# LPTSV2_usingATmega328PV6.net
KiCad netlist of a schematic drawn in EAGLE
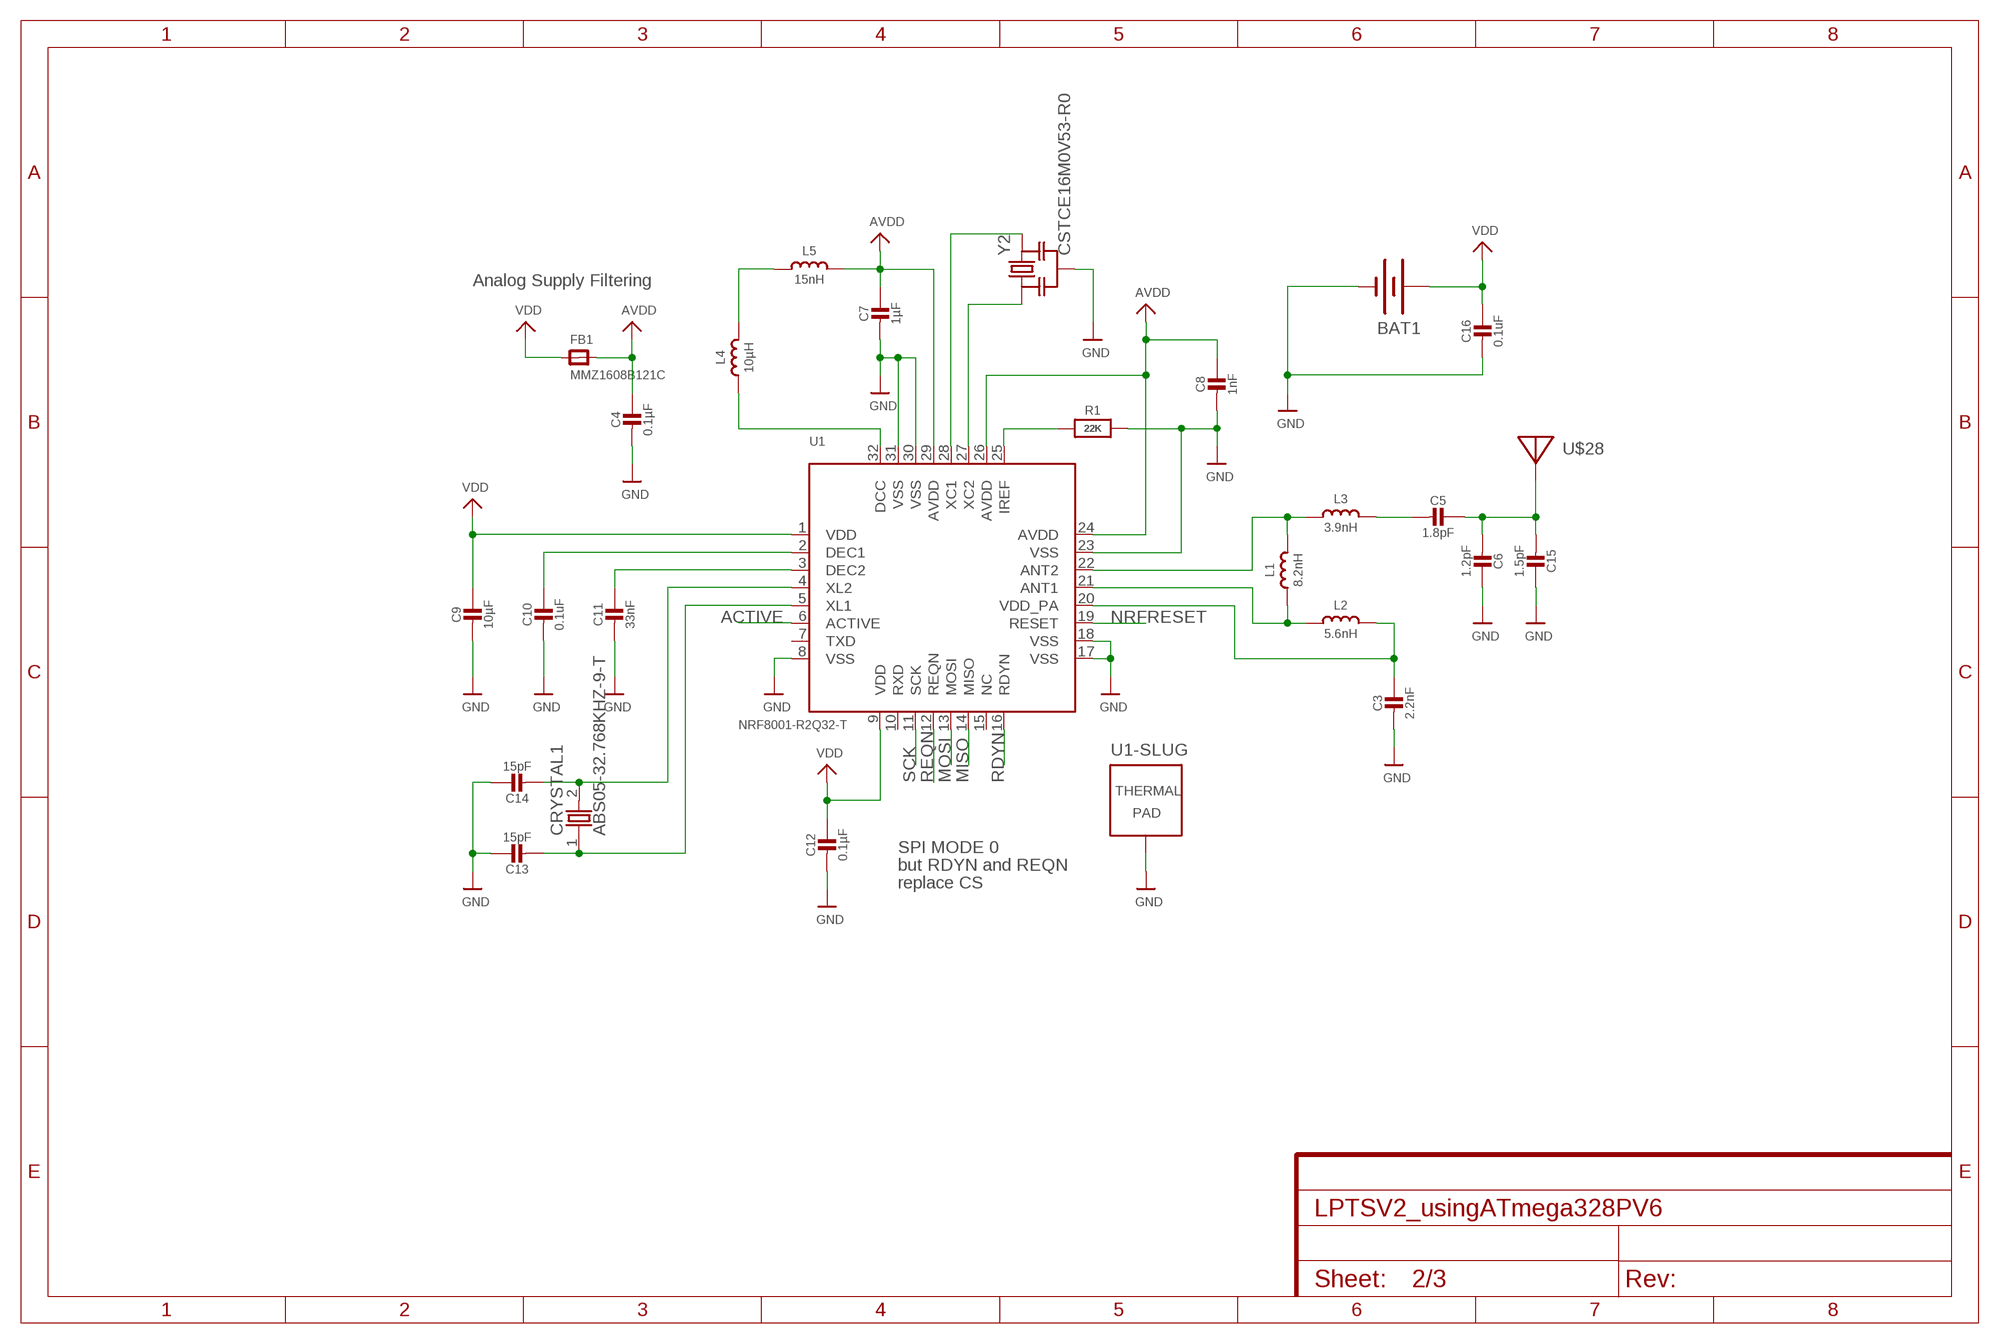
[diagram p0: schematic, sheet 2]
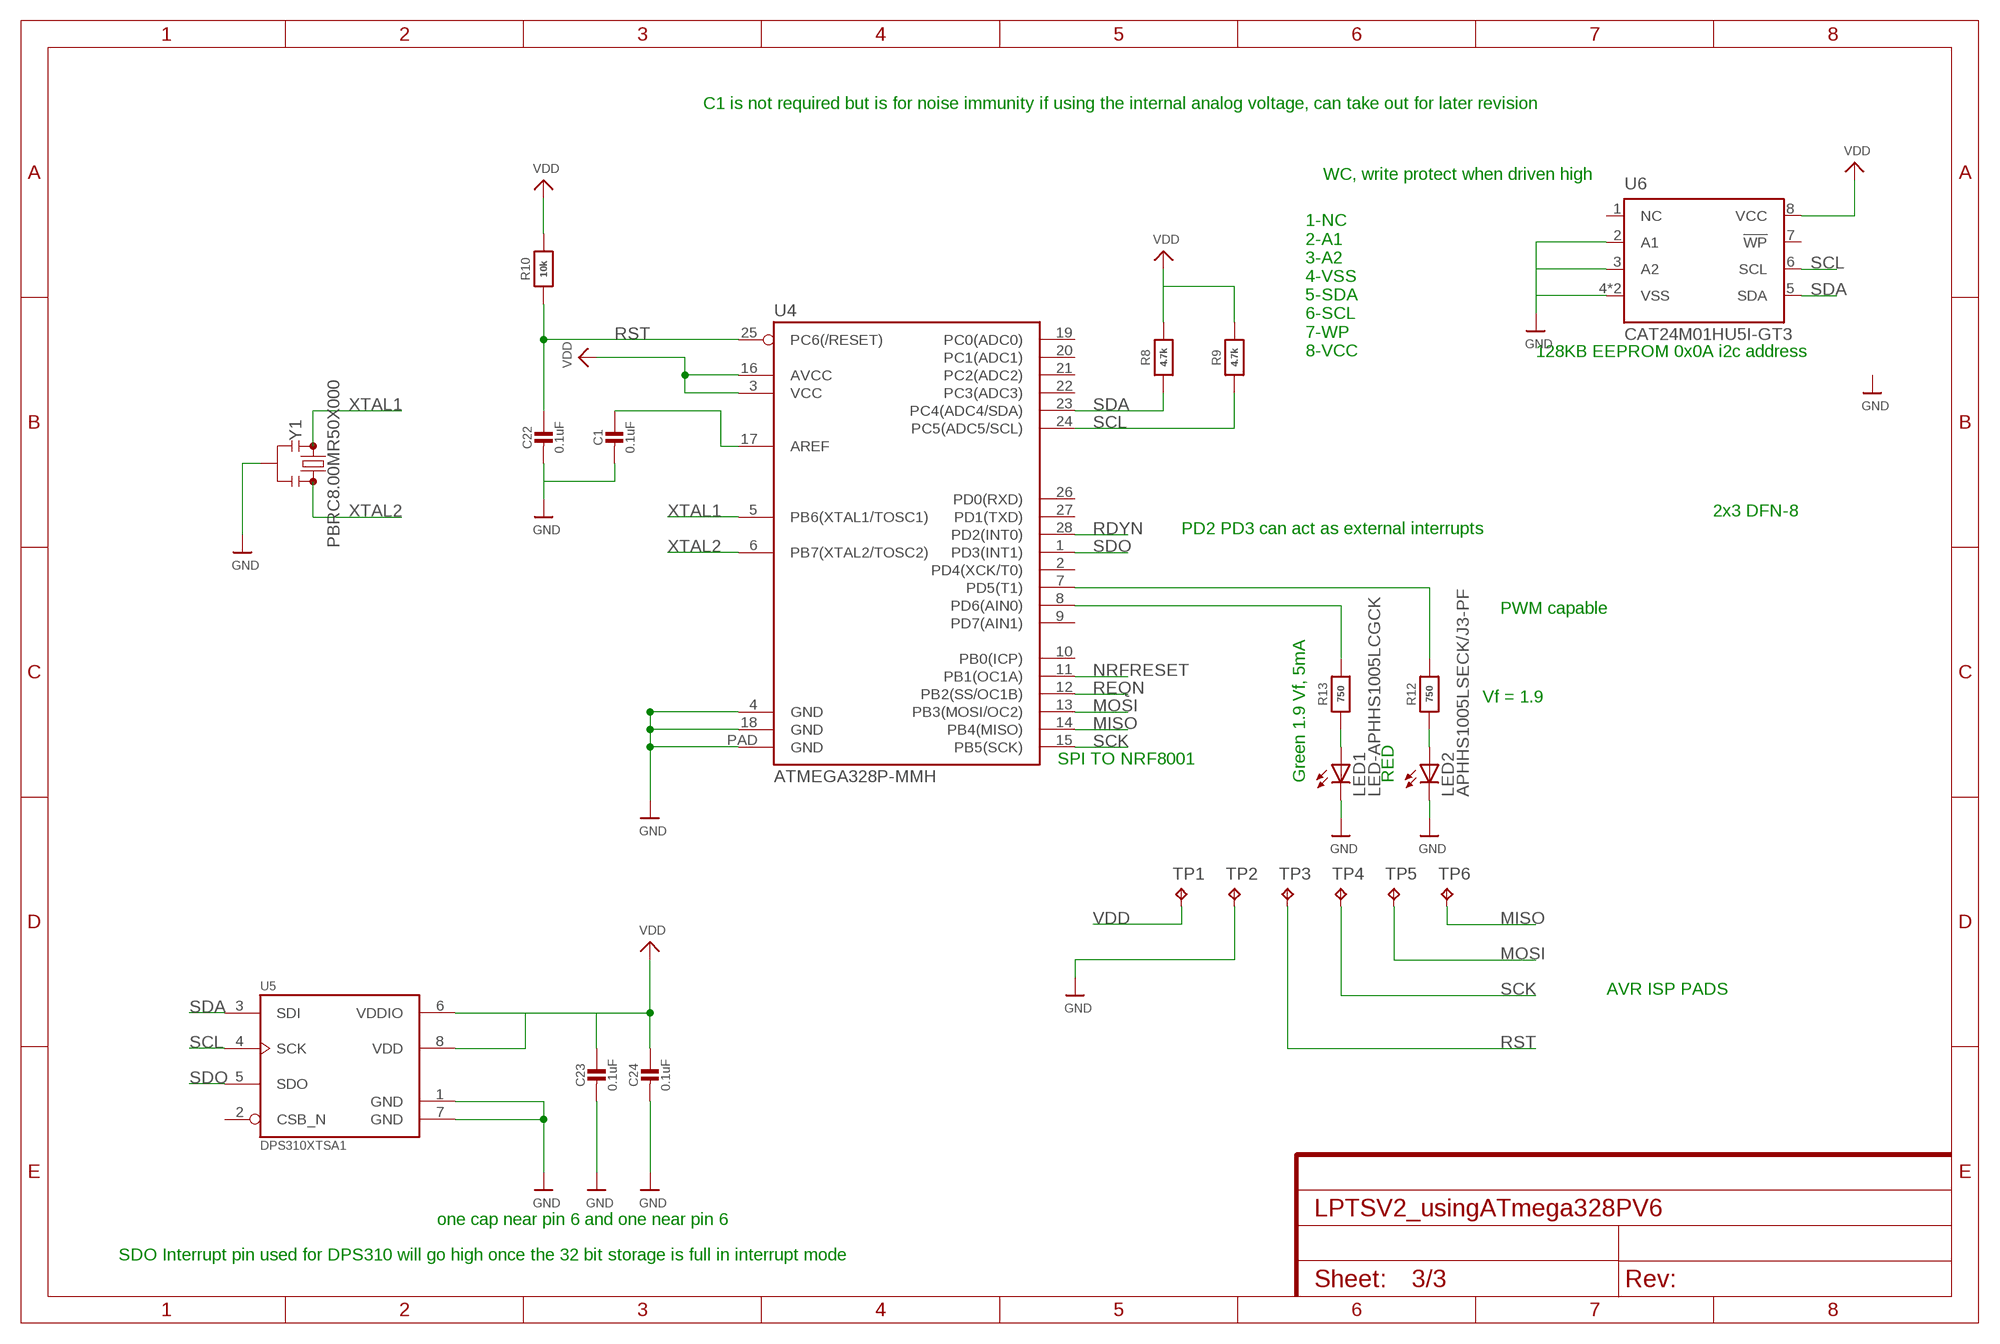
[diagram p1: schematic, sheet 3]

(export (version "E")
  (design (tool "Eeschema 10.0.6"))
  (components
    (comp (ref "C1")
      (value "0.1uF")
      (footprint "eagle-import:_0402")
      (fields (field (name "PARTNUMBER") "GRM155R71C104KA88J"))
      (libsource (lib "eagle-import") (part "CAP_CERAMIC_0402"))
    )
    (comp (ref "C22")
      (value "0.1uF")
      (footprint "eagle-import:_0402")
      (fields (field (name "PARTNUMBER") "GRM155R71C104KA88J"))
      (libsource (lib "eagle-import") (part "CAP_CERAMIC_0402"))
    )
    (comp (ref "C23")
      (value "0.1uF")
      (footprint "eagle-import:_0402")
      (fields (field (name "PARTNUMBER") "GRM155R71C104KA88J"))
      (libsource (lib "eagle-import") (part "CAP_CERAMIC_0402"))
    )
    (comp (ref "C24")
      (value "0.1uF")
      (footprint "eagle-import:_0402")
      (fields (field (name "PARTNUMBER") "GRM155R71C104KA88J"))
      (libsource (lib "eagle-import") (part "CAP_CERAMIC_0402"))
    )
    (comp (ref "LED1")
      (value "LED-APHHS1005LCGCK")
      (footprint "eagle-import:0402-LED")
      (libsource (lib "eagle-import") (part "LED-0402"))
    )
    (comp (ref "LED2")
      (value "APHHS1005LSECK/J3-PF")
      (footprint "eagle-import:0402-LED")
      (libsource (lib "eagle-import") (part "LED-0402"))
    )
    (comp (ref "R8")
      (value "4.7k")
      (footprint "eagle-import:_0402")
      (fields (field (name "PARTNUMBER") "RC0402JR-074K7L"))
      (libsource (lib "eagle-import") (part "RESISTOR_0402"))
    )
    (comp (ref "R9")
      (value "4.7k")
      (footprint "eagle-import:_0402")
      (fields (field (name "PARTNUMBER") "RC0402JR-074K7L"))
      (libsource (lib "eagle-import") (part "RESISTOR_0402"))
    )
    (comp (ref "R10")
      (value "10k")
      (footprint "eagle-import:_0402")
      (fields (field (name "PARTNUMBER") "RC0402JR-0710KL"))
      (libsource (lib "eagle-import") (part "RESISTOR_0402"))
    )
    (comp (ref "R12")
      (value "750")
      (footprint "eagle-import:_0402")
      (fields (field (name "PARTNUMBER") "RC0402JR-07750RL"))
      (libsource (lib "eagle-import") (part "RESISTOR_0402"))
    )
    (comp (ref "R13")
      (value "750")
      (footprint "eagle-import:_0402")
      (fields (field (name "PARTNUMBER") "RC0402JR-07750RL"))
      (libsource (lib "eagle-import") (part "RESISTOR_0402"))
    )
    (comp (ref "TP1")
      (value "TPTP10SQ")
      (footprint "eagle-import:TP10SQ")
      (libsource (lib "eagle-import") (part "TPTP10SQ"))
    )
    (comp (ref "TP2")
      (value "TPTP10SQ")
      (footprint "eagle-import:TP10SQ")
      (libsource (lib "eagle-import") (part "TPTP10SQ"))
    )
    (comp (ref "TP3")
      (value "TPTP10SQ")
      (footprint "eagle-import:TP10SQ")
      (libsource (lib "eagle-import") (part "TPTP10SQ"))
    )
    (comp (ref "TP4")
      (value "TPTP10SQ")
      (footprint "eagle-import:TP10SQ")
      (libsource (lib "eagle-import") (part "TPTP10SQ"))
    )
    (comp (ref "TP5")
      (value "TPTP10SQ")
      (footprint "eagle-import:TP10SQ")
      (libsource (lib "eagle-import") (part "TPTP10SQ"))
    )
    (comp (ref "TP6")
      (value "TPTP10SQ")
      (footprint "eagle-import:TP10SQ")
      (libsource (lib "eagle-import") (part "TPTP10SQ"))
    )
    (comp (ref "U4")
      (value "ATMEGA328P-MMH")
      (footprint "eagle-import:SPARKFUN-IC-MICROCONTROLLER_VQFN-28")
      (libsource (lib "eagle-import") (part "SPARKFUN-IC-MICROCONTROLLER_ATMEGA328P_VQFNVQFN"))
    )
    (comp (ref "U5")
      (value "DPS310XTSA1")
      (footprint "eagle-import:LGA8S145X65P2X4_200X250X100")
      (libsource (lib "eagle-import") (part "DPS310"))
    )
    (comp (ref "U6")
      (value "CAT24M01HU5I-GT3")
      (footprint "eagle-import:DFN-2X3")
      (libsource (lib "eagle-import") (part "CAT24M01HU5I-GT3"))
    )
    (comp (ref "Y1")
      (value "PBRC8.00MR50X000")
      (footprint "eagle-import:RESONATOR-SMD-4.5X2.0")
      (libsource (lib "eagle-import") (part "RESONATOR-4MHZSMD-4.5X2"))
    )
    (comp (ref "BAT1")
      (value "LINX-BAT-HLD-00120SMD")
      (footprint "eagle-import:BATTCON_20MM")
      (fields (field (name "PARTNUMBER") "BAT-HLD-001-TRCT-ND"))
      (libsource (lib "eagle-import") (part "LINX-BAT-HLD-00120SMD"))
    )
    (comp (ref "C3")
      (value "2.2nF")
      (footprint "eagle-import:_0402")
      (fields (field (name "PARTNUMBER") "C0402C222J8JAC7867"))
      (libsource (lib "eagle-import") (part "CAP_CERAMIC_0402"))
    )
    (comp (ref "C4")
      (value "0.1µF")
      (footprint "eagle-import:_0402")
      (fields (field (name "PARTNUMBER") "GRM155R71C104KA88J"))
      (libsource (lib "eagle-import") (part "CAP_CERAMIC_0402"))
    )
    (comp (ref "C5")
      (value "1.8pF")
      (footprint "eagle-import:_0402MP")
      (fields (field (name "PARTNUMBER") "GRM1555C1E1R8BA01D"))
      (libsource (lib "eagle-import") (part "CAP_CERAMIC_0402MP"))
    )
    (comp (ref "C6")
      (value "1.2pF")
      (footprint "eagle-import:_0402MP")
      (fields (field (name "PARTNUMBER") "GRM1555C1E1R2BA01D"))
      (libsource (lib "eagle-import") (part "CAP_CERAMIC_0402MP"))
    )
    (comp (ref "C7")
      (value "1µF")
      (footprint "eagle-import:_0402")
      (fields (field (name "PARTNUMBER") "0402ZD105KAT2A"))
      (libsource (lib "eagle-import") (part "CAP_CERAMIC_0402"))
    )
    (comp (ref "C8")
      (value "1nF")
      (footprint "eagle-import:_0402")
      (fields (field (name "PARTNUMBER") "GRM155R71H102KA01D"))
      (libsource (lib "eagle-import") (part "CAP_CERAMIC_0402"))
    )
    (comp (ref "C9")
      (value "10µF")
      (footprint "eagle-import:_0402")
      (fields (field (name "PARTNUMBER") "GRM155R60J106ME15D"))
      (libsource (lib "eagle-import") (part "CAP_CERAMIC_0402"))
    )
    (comp (ref "C10")
      (value "0.1uF")
      (footprint "eagle-import:_0402")
      (fields (field (name "PARTNUMBER") "GRM155R71C104KA88J"))
      (libsource (lib "eagle-import") (part "CAP_CERAMIC_0402"))
    )
    (comp (ref "C11")
      (value "33nF")
      (footprint "eagle-import:_0402")
      (fields (field (name "PARTNUMBER") "C0402C333K8RACTU"))
      (libsource (lib "eagle-import") (part "CAP_CERAMIC_0402"))
    )
    (comp (ref "C12")
      (value "0.1µF")
      (footprint "eagle-import:_0402")
      (fields (field (name "PARTNUMBER") "GRM155R71C104KA88J"))
      (libsource (lib "eagle-import") (part "CAP_CERAMIC_0402"))
    )
    (comp (ref "C13")
      (value "15pF")
      (footprint "eagle-import:_0402")
      (fields (field (name "PARTNUMBER") "GRM1555C1H150JA01D"))
      (libsource (lib "eagle-import") (part "CAP_CERAMIC_0402"))
    )
    (comp (ref "C14")
      (value "15pF")
      (footprint "eagle-import:_0402")
      (fields (field (name "PARTNUMBER") "GRM1555C1H150JA01D"))
      (libsource (lib "eagle-import") (part "CAP_CERAMIC_0402"))
    )
    (comp (ref "C15")
      (value "1.5pF")
      (footprint "eagle-import:_0402MP")
      (fields (field (name "PARTNUMBER") "GRM1555C1H1R5BA01D"))
      (libsource (lib "eagle-import") (part "CAP_CERAMIC_0402MP"))
    )
    (comp (ref "C16")
      (value "0.1uF")
      (footprint "eagle-import:_0402")
      (fields (field (name "PARTNUMBER") "GRM155R71C104KA88J"))
      (libsource (lib "eagle-import") (part "CAP_CERAMIC_0402"))
    )
    (comp (ref "CRYSTAL1")
      (value "ABS05-32.768KHZ-9-T")
      (footprint "eagle-import:CRYSTAL-2PIN")
      (libsource (lib "eagle-import") (part "CRYSTAL2PIN"))
    )
    (comp (ref "FB1")
      (value "MMZ1608B121C")
      (footprint "eagle-import:0805")
      (fields (field (name "PARTNUMBER") "MMZ1608B121CTDH5"))
      (libsource (lib "eagle-import") (part "FERRITE0805"))
    )
    (comp (ref "L1")
      (value "8.2nH")
      (footprint "eagle-import:_0402")
      (fields (field (name "PARTNUMBER") "LQP15MN8N2B02D"))
      (libsource (lib "eagle-import") (part "INDUCTOR_0402"))
    )
    (comp (ref "L2")
      (value "5.6nH")
      (footprint "eagle-import:_0402")
      (fields (field (name "PARTNUMBER") "LQP15MN5N6B02D"))
      (libsource (lib "eagle-import") (part "INDUCTOR_0402"))
    )
    (comp (ref "L3")
      (value "3.9nH")
      (footprint "eagle-import:_0402")
      (fields (field (name "PARTNUMBER") "LQP03TN3N9B02D"))
      (libsource (lib "eagle-import") (part "INDUCTOR_0402"))
    )
    (comp (ref "L4")
      (value "10µH")
      (footprint "eagle-import:_0603")
      (fields (field (name "PARTNUMBER") "LBMF1608T100K"))
      (libsource (lib "eagle-import") (part "INDUCTOR_0603"))
    )
    (comp (ref "L5")
      (value "15nH")
      (footprint "eagle-import:_0603")
      (fields (field (name "PARTNUMBER") "L-14C15NJV4T"))
      (libsource (lib "eagle-import") (part "INDUCTOR_0603"))
    )
    (comp (ref "R1")
      (value "22K")
      (footprint "eagle-import:_0805")
      (fields (field (name "PARTNUMBER") "RC0805JR-0722KL"))
      (libsource (lib "eagle-import") (part "RESISTOR_0805"))
    )
    (comp (ref "U$28")
      (value "ANTENNA_PCBNRF8001_1.6MM")
      (footprint "eagle-import:ANT_PCB_2.4GHZ_NRF8001_1.6MM_1OZ")
      (libsource (lib "eagle-import") (part "ANTENNA_PCBNRF8001_1.6MM"))
    )
    (comp (ref "U1")
      (value "NRF8001-R2Q32-T")
      (footprint "eagle-import:MICROBUILDER_QFN32_5MM")
      (libsource (lib "eagle-import") (part "MICROBUILDER_NRF8001"))
    )
    (comp (ref "Y2")
      (value "CSTCE16M0V53-R0")
      (footprint "eagle-import:RESONATOR_MURATA2")
      (libsource (lib "eagle-import") (part "RESONATOR-MURATACST_CE"))
    )
  )
  (nets
    (net (code "1") (name "ACTIVE") (class "Default")
      (node (ref "U1") (pin "6") (pinfunction "ACTIVE_6") (pintype "output"))
    )
    (net (code "2") (name "AVDD") (class "Default")
      (node (ref "C4") (pin "1") (pinfunction "1_1") (pintype "passive"))
      (node (ref "C7") (pin "1") (pinfunction "1_1") (pintype "passive"))
      (node (ref "C8") (pin "1") (pinfunction "1_1") (pintype "passive"))
      (node (ref "FB1") (pin "2") (pinfunction "P$2_2") (pintype "passive"))
      (node (ref "L5") (pin "2") (pinfunction "2_2") (pintype "passive"))
      (node (ref "U1") (pin "24") (pinfunction "AVDD_24") (pintype "power_in"))
      (node (ref "U1") (pin "26") (pinfunction "AVDD_26") (pintype "power_in"))
      (node (ref "U1") (pin "29") (pinfunction "AVDD_29") (pintype "power_in"))
    )
    (net (code "3") (name "GND") (class "Default")
      (node (ref "BAT1") (pin "2") (pinfunction "-_2") (pintype "power_in"))
      (node (ref "C1") (pin "2") (pinfunction "2_2") (pintype "passive"))
      (node (ref "C10") (pin "2") (pinfunction "2_2") (pintype "passive"))
      (node (ref "C11") (pin "2") (pinfunction "2_2") (pintype "passive"))
      (node (ref "C12") (pin "2") (pinfunction "2_2") (pintype "passive"))
      (node (ref "C13") (pin "1") (pinfunction "1_1") (pintype "passive"))
      (node (ref "C14") (pin "1") (pinfunction "1_1") (pintype "passive"))
      (node (ref "C15") (pin "1") (pinfunction "1_1") (pintype "passive"))
      (node (ref "C16") (pin "2") (pinfunction "2_2") (pintype "passive"))
      (node (ref "C22") (pin "2") (pinfunction "2_2") (pintype "passive"))
      (node (ref "C23") (pin "2") (pinfunction "2_2") (pintype "passive"))
      (node (ref "C24") (pin "2") (pinfunction "2_2") (pintype "passive"))
      (node (ref "C3") (pin "2") (pinfunction "2_2") (pintype "passive"))
      (node (ref "C4") (pin "2") (pinfunction "2_2") (pintype "passive"))
      (node (ref "C6") (pin "1") (pinfunction "1_1") (pintype "passive"))
      (node (ref "C7") (pin "2") (pinfunction "2_2") (pintype "passive"))
      (node (ref "C8") (pin "2") (pinfunction "2_2") (pintype "passive"))
      (node (ref "C9") (pin "2") (pinfunction "2_2") (pintype "passive"))
      (node (ref "LED1") (pin "C") (pinfunction "C_C") (pintype "passive"))
      (node (ref "LED2") (pin "C") (pinfunction "C_C") (pintype "passive"))
      (node (ref "R1") (pin "2") (pinfunction "2_2") (pintype "passive"))
      (node (ref "TP2") (pin "TP") (pinfunction "TP_TP") (pintype "input"))
      (node (ref "U1") (pin "17") (pinfunction "VSS_17") (pintype "power_in"))
      (node (ref "U1") (pin "18") (pinfunction "VSS_18") (pintype "power_in"))
      (node (ref "U1") (pin "23") (pinfunction "VSS_23") (pintype "power_in"))
      (node (ref "U1") (pin "30") (pinfunction "VSS_30") (pintype "power_in"))
      (node (ref "U1") (pin "31") (pinfunction "VSS_31") (pintype "power_in"))
      (node (ref "U1") (pin "33") (pinfunction "TP_33") (pintype "power_in"))
      (node (ref "U1") (pin "8") (pinfunction "VSS_8") (pintype "power_in"))
      (node (ref "U4") (pin "18") (pinfunction "GND_18") (pintype "bidirectional"))
      (node (ref "U4") (pin "4") (pinfunction "GND_4") (pintype "bidirectional"))
      (node (ref "U4") (pin "PAD") (pinfunction "GND_PAD") (pintype "bidirectional"))
      (node (ref "U5") (pin "1") (pinfunction "GND_1") (pintype "power_in"))
      (node (ref "U5") (pin "7") (pinfunction "GND_7") (pintype "power_in"))
      (node (ref "U6") (pin "2") (pinfunction "A1_2") (pintype "input"))
      (node (ref "U6") (pin "3") (pinfunction "A2_3") (pintype "input"))
      (node (ref "U6") (pin "4") (pinfunction "VSS_4") (pintype "power_in"))
      (node (ref "U6") (pin "EXP") (pinfunction "VSS_EXP") (pintype "power_in"))
      (node (ref "Y1") (pin "2") (pinfunction "2_2") (pintype "passive"))
      (node (ref "Y2") (pin "2") (pinfunction "2_2") (pintype "passive"))
    )
    (net (code "4") (name "MISO") (class "Default")
      (node (ref "TP6") (pin "TP") (pinfunction "TP_TP") (pintype "input"))
      (node (ref "U1") (pin "14") (pinfunction "MISO_14") (pintype "output"))
      (node (ref "U4") (pin "14") (pinfunction "PB4(MISO)_14") (pintype "bidirectional"))
    )
    (net (code "5") (name "MOSI") (class "Default")
      (node (ref "TP5") (pin "TP") (pinfunction "TP_TP") (pintype "input"))
      (node (ref "U1") (pin "13") (pinfunction "MOSI_13") (pintype "input"))
      (node (ref "U4") (pin "13") (pinfunction "PB3(MOSI/OC2)_13") (pintype "bidirectional"))
    )
    (net (code "6") (name "NRFRESET") (class "Default")
      (node (ref "U1") (pin "19") (pinfunction "RESET_19") (pintype "input"))
      (node (ref "U4") (pin "11") (pinfunction "PB1(OC1A)_11") (pintype "bidirectional"))
    )
    (net (code "7") (name "Net-(C5-Pad2)") (class "Default")
      (node (ref "C5") (pin "2") (pinfunction "2_2") (pintype "passive"))
      (node (ref "L3") (pin "2") (pinfunction "2_2") (pintype "passive"))
    )
    (net (code "8") (name "Net-(L4-Pad2)") (class "Default")
      (node (ref "L4") (pin "2") (pinfunction "2_2") (pintype "passive"))
      (node (ref "L5") (pin "1") (pinfunction "1_1") (pintype "passive"))
    )
    (net (code "9") (name "Net-(LED1-PadA)") (class "Default")
      (node (ref "LED1") (pin "A") (pinfunction "A_A") (pintype "passive"))
      (node (ref "R13") (pin "1") (pinfunction "1_1") (pintype "passive"))
    )
    (net (code "10") (name "Net-(LED2-PadA)") (class "Default")
      (node (ref "LED2") (pin "A") (pinfunction "A_A") (pintype "passive"))
      (node (ref "R12") (pin "1") (pinfunction "1_1") (pintype "passive"))
    )
    (net (code "11") (name "Net-(U$28-P$1)") (class "Default")
      (node (ref "C15") (pin "2") (pinfunction "2_2") (pintype "passive"))
      (node (ref "C5") (pin "1") (pinfunction "1_1") (pintype "passive"))
      (node (ref "C6") (pin "2") (pinfunction "2_2") (pintype "passive"))
      (node (ref "U$28") (pin "FEED") (pinfunction "P$1_FEED") (pintype "passive"))
    )
    (net (code "12") (name "Net-(U1B-ANT1)") (class "Default")
      (node (ref "L1") (pin "1") (pinfunction "1_1") (pintype "passive"))
      (node (ref "L2") (pin "1") (pinfunction "1_1") (pintype "passive"))
      (node (ref "U1") (pin "21") (pinfunction "ANT1_21") (pintype "bidirectional"))
    )
    (net (code "13") (name "Net-(U1B-ANT2)") (class "Default")
      (node (ref "L1") (pin "2") (pinfunction "2_2") (pintype "passive"))
      (node (ref "L3") (pin "1") (pinfunction "1_1") (pintype "passive"))
      (node (ref "U1") (pin "22") (pinfunction "ANT2_22") (pintype "bidirectional"))
    )
    (net (code "14") (name "Net-(U1B-DCC)") (class "Default")
      (node (ref "L4") (pin "1") (pinfunction "1_1") (pintype "passive"))
      (node (ref "U1") (pin "32") (pinfunction "DCC_32") (pintype "bidirectional"))
    )
    (net (code "15") (name "Net-(U1B-DEC1)") (class "Default")
      (node (ref "C10") (pin "1") (pinfunction "1_1") (pintype "passive"))
      (node (ref "U1") (pin "2") (pinfunction "DEC1_2") (pintype "bidirectional"))
    )
    (net (code "16") (name "Net-(U1B-DEC2)") (class "Default")
      (node (ref "C11") (pin "1") (pinfunction "1_1") (pintype "passive"))
      (node (ref "U1") (pin "3") (pinfunction "DEC2_3") (pintype "bidirectional"))
    )
    (net (code "17") (name "Net-(U1B-IREF)") (class "Default")
      (node (ref "R1") (pin "1") (pinfunction "1_1") (pintype "passive"))
      (node (ref "U1") (pin "25") (pinfunction "IREF_25") (pintype "output"))
    )
    (net (code "18") (name "Net-(U1B-VDD_PA)") (class "Default")
      (node (ref "C3") (pin "1") (pinfunction "1_1") (pintype "passive"))
      (node (ref "L2") (pin "2") (pinfunction "2_2") (pintype "passive"))
      (node (ref "U1") (pin "20") (pinfunction "VDD_PA_20") (pintype "bidirectional"))
    )
    (net (code "19") (name "Net-(U1B-XC1)") (class "Default")
      (node (ref "U1") (pin "28") (pinfunction "XC1_28") (pintype "input"))
      (node (ref "Y2") (pin "3") (pinfunction "3_3") (pintype "passive"))
    )
    (net (code "20") (name "Net-(U1B-XC2)") (class "Default")
      (node (ref "U1") (pin "27") (pinfunction "XC2_27") (pintype "output"))
      (node (ref "Y2") (pin "1") (pinfunction "1_1") (pintype "passive"))
    )
    (net (code "21") (name "Net-(U1B-XL1)") (class "Default")
      (node (ref "C13") (pin "2") (pinfunction "2_2") (pintype "passive"))
      (node (ref "CRYSTAL1") (pin "1") (pinfunction "1_1") (pintype "passive"))
      (node (ref "U1") (pin "5") (pinfunction "XL1_5") (pintype "input"))
    )
    (net (code "22") (name "Net-(U1B-XL2)") (class "Default")
      (node (ref "C14") (pin "2") (pinfunction "2_2") (pintype "passive"))
      (node (ref "CRYSTAL1") (pin "2") (pinfunction "2_2") (pintype "passive"))
      (node (ref "U1") (pin "4") (pinfunction "XL2_4") (pintype "output"))
    )
    (net (code "23") (name "Net-(U4-AREF)") (class "Default")
      (node (ref "C1") (pin "1") (pinfunction "1_1") (pintype "passive"))
      (node (ref "U4") (pin "17") (pinfunction "AREF_17") (pintype "bidirectional"))
    )
    (net (code "24") (name "Net-(U4-PD5(T1))") (class "Default")
      (node (ref "R12") (pin "2") (pinfunction "2_2") (pintype "passive"))
      (node (ref "U4") (pin "7") (pinfunction "PD5(T1)_7") (pintype "bidirectional"))
    )
    (net (code "25") (name "Net-(U4-PD6(AIN0))") (class "Default")
      (node (ref "R13") (pin "2") (pinfunction "2_2") (pintype "passive"))
      (node (ref "U4") (pin "8") (pinfunction "PD6(AIN0)_8") (pintype "bidirectional"))
    )
    (net (code "26") (name "RDYN") (class "Default")
      (node (ref "U1") (pin "16") (pinfunction "RDYN_16") (pintype "output"))
      (node (ref "U4") (pin "28") (pinfunction "PD2(INT0)_28") (pintype "bidirectional"))
    )
    (net (code "27") (name "REQN") (class "Default")
      (node (ref "U1") (pin "12") (pinfunction "REQN_12") (pintype "input"))
      (node (ref "U4") (pin "12") (pinfunction "PB2(SS/OC1B)_12") (pintype "bidirectional"))
    )
    (net (code "28") (name "RST") (class "Default")
      (node (ref "C22") (pin "1") (pinfunction "1_1") (pintype "passive"))
      (node (ref "R10") (pin "1") (pinfunction "1_1") (pintype "passive"))
      (node (ref "TP3") (pin "TP") (pinfunction "TP_TP") (pintype "input"))
      (node (ref "U4") (pin "25") (pinfunction "PC6(/RESET)_25") (pintype "bidirectional"))
    )
    (net (code "29") (name "SCK") (class "Default")
      (node (ref "TP4") (pin "TP") (pinfunction "TP_TP") (pintype "input"))
      (node (ref "U1") (pin "11") (pinfunction "SCK_11") (pintype "input"))
      (node (ref "U4") (pin "15") (pinfunction "PB5(SCK)_15") (pintype "bidirectional"))
    )
    (net (code "30") (name "SCL") (class "Default")
      (node (ref "R9") (pin "1") (pinfunction "1_1") (pintype "passive"))
      (node (ref "U4") (pin "24") (pinfunction "PC5(ADC5/SCL)_24") (pintype "bidirectional"))
      (node (ref "U5") (pin "4") (pinfunction "SCK_4") (pintype "input"))
      (node (ref "U6") (pin "6") (pinfunction "SCL_6") (pintype "input"))
    )
    (net (code "31") (name "SDA") (class "Default")
      (node (ref "R8") (pin "1") (pinfunction "1_1") (pintype "passive"))
      (node (ref "U4") (pin "23") (pinfunction "PC4(ADC4/SDA)_23") (pintype "bidirectional"))
      (node (ref "U5") (pin "3") (pinfunction "SDI_3") (pintype "bidirectional"))
      (node (ref "U6") (pin "5") (pinfunction "SDA_5") (pintype "output"))
    )
    (net (code "32") (name "SDO") (class "Default")
      (node (ref "U4") (pin "1") (pinfunction "PD3(INT1)_1") (pintype "bidirectional"))
      (node (ref "U5") (pin "5") (pinfunction "SDO_5") (pintype "output"))
    )
    (net (code "33") (name "VDD") (class "Default")
      (node (ref "BAT1") (pin "1") (pinfunction "+_1") (pintype "power_in"))
      (node (ref "BAT1") (pin "3") (pinfunction "+_3") (pintype "power_in"))
      (node (ref "C12") (pin "1") (pinfunction "1_1") (pintype "passive"))
      (node (ref "C16") (pin "1") (pinfunction "1_1") (pintype "passive"))
      (node (ref "C23") (pin "1") (pinfunction "1_1") (pintype "passive"))
      (node (ref "C24") (pin "1") (pinfunction "1_1") (pintype "passive"))
      (node (ref "C9") (pin "1") (pinfunction "1_1") (pintype "passive"))
      (node (ref "FB1") (pin "1") (pinfunction "P$1_1") (pintype "passive"))
      (node (ref "R10") (pin "2") (pinfunction "2_2") (pintype "passive"))
      (node (ref "R8") (pin "2") (pinfunction "2_2") (pintype "passive"))
      (node (ref "R9") (pin "2") (pinfunction "2_2") (pintype "passive"))
      (node (ref "TP1") (pin "TP") (pinfunction "TP_TP") (pintype "input"))
      (node (ref "U1") (pin "1") (pinfunction "VDD_1") (pintype "power_in"))
      (node (ref "U1") (pin "9") (pinfunction "VDD_9") (pintype "power_in"))
      (node (ref "U4") (pin "16") (pinfunction "AVCC_16") (pintype "bidirectional"))
      (node (ref "U4") (pin "3") (pinfunction "VCC_3") (pintype "bidirectional"))
      (node (ref "U5") (pin "6") (pinfunction "VDDIO_6") (pintype "power_in"))
      (node (ref "U5") (pin "8") (pinfunction "VDD_8") (pintype "power_in"))
      (node (ref "U6") (pin "8") (pinfunction "VCC_8") (pintype "power_in"))
    )
    (net (code "34") (name "XTAL1") (class "Default")
      (node (ref "U4") (pin "5") (pinfunction "PB6(XTAL1/TOSC1)_5") (pintype "bidirectional"))
      (node (ref "Y1") (pin "1") (pinfunction "1_1") (pintype "passive"))
    )
    (net (code "35") (name "XTAL2") (class "Default")
      (node (ref "U4") (pin "6") (pinfunction "PB7(XTAL2/TOSC2)_6") (pintype "bidirectional"))
      (node (ref "Y1") (pin "3") (pinfunction "3_3") (pintype "passive"))
    )
    (net (code "36") (name "unconnected-(U1B-NC-Pad15)") (class "Default")
      (node (ref "U1") (pin "15") (pinfunction "NC_15") (pintype "no_connect"))
    )
    (net (code "37") (name "unconnected-(U1B-RXD-Pad10)") (class "Default")
      (node (ref "U1") (pin "10") (pinfunction "RXD_10") (pintype "input"))
    )
    (net (code "38") (name "unconnected-(U1B-TXD-Pad7)") (class "Default")
      (node (ref "U1") (pin "7") (pinfunction "TXD_7") (pintype "output"))
    )
    (net (code "39") (name "unconnected-(U4-PB0(ICP)-Pad10)") (class "Default")
      (node (ref "U4") (pin "10") (pinfunction "PB0(ICP)_10") (pintype "bidirectional"))
    )
    (net (code "40") (name "unconnected-(U4-PC0(ADC0)-Pad19)") (class "Default")
      (node (ref "U4") (pin "19") (pinfunction "PC0(ADC0)_19") (pintype "bidirectional"))
    )
    (net (code "41") (name "unconnected-(U4-PC1(ADC1)-Pad20)") (class "Default")
      (node (ref "U4") (pin "20") (pinfunction "PC1(ADC1)_20") (pintype "bidirectional"))
    )
    (net (code "42") (name "unconnected-(U4-PC2(ADC2)-Pad21)") (class "Default")
      (node (ref "U4") (pin "21") (pinfunction "PC2(ADC2)_21") (pintype "bidirectional"))
    )
    (net (code "43") (name "unconnected-(U4-PC3(ADC3)-Pad22)") (class "Default")
      (node (ref "U4") (pin "22") (pinfunction "PC3(ADC3)_22") (pintype "bidirectional"))
    )
    (net (code "44") (name "unconnected-(U4-PD0(RXD)-Pad26)") (class "Default")
      (node (ref "U4") (pin "26") (pinfunction "PD0(RXD)_26") (pintype "bidirectional"))
    )
    (net (code "45") (name "unconnected-(U4-PD1(TXD)-Pad27)") (class "Default")
      (node (ref "U4") (pin "27") (pinfunction "PD1(TXD)_27") (pintype "bidirectional"))
    )
    (net (code "46") (name "unconnected-(U4-PD4(XCK{slash}T0)-Pad2)") (class "Default")
      (node (ref "U4") (pin "2") (pinfunction "PD4(XCK/T0)_2") (pintype "bidirectional"))
    )
    (net (code "47") (name "unconnected-(U4-PD7(AIN1)-Pad9)") (class "Default")
      (node (ref "U4") (pin "9") (pinfunction "PD7(AIN1)_9") (pintype "bidirectional"))
    )
    (net (code "48") (name "unconnected-(U5-CSB_N-Pad2)") (class "Default")
      (node (ref "U5") (pin "2") (pinfunction "CSB_N_2") (pintype "input"))
    )
    (net (code "49") (name "unconnected-(U6-NC-Pad1)") (class "Default")
      (node (ref "U6") (pin "1") (pinfunction "NC_1") (pintype "no_connect"))
    )
    (net (code "50") (name "unconnected-(U6-~{WP}-Pad7)") (class "Default")
      (node (ref "U6") (pin "7") (pinfunction "~{WP}_7") (pintype "input"))
    )
  )
)
